# Qilin.net
KiCad netlist of a schematic drawn in Altium Designer
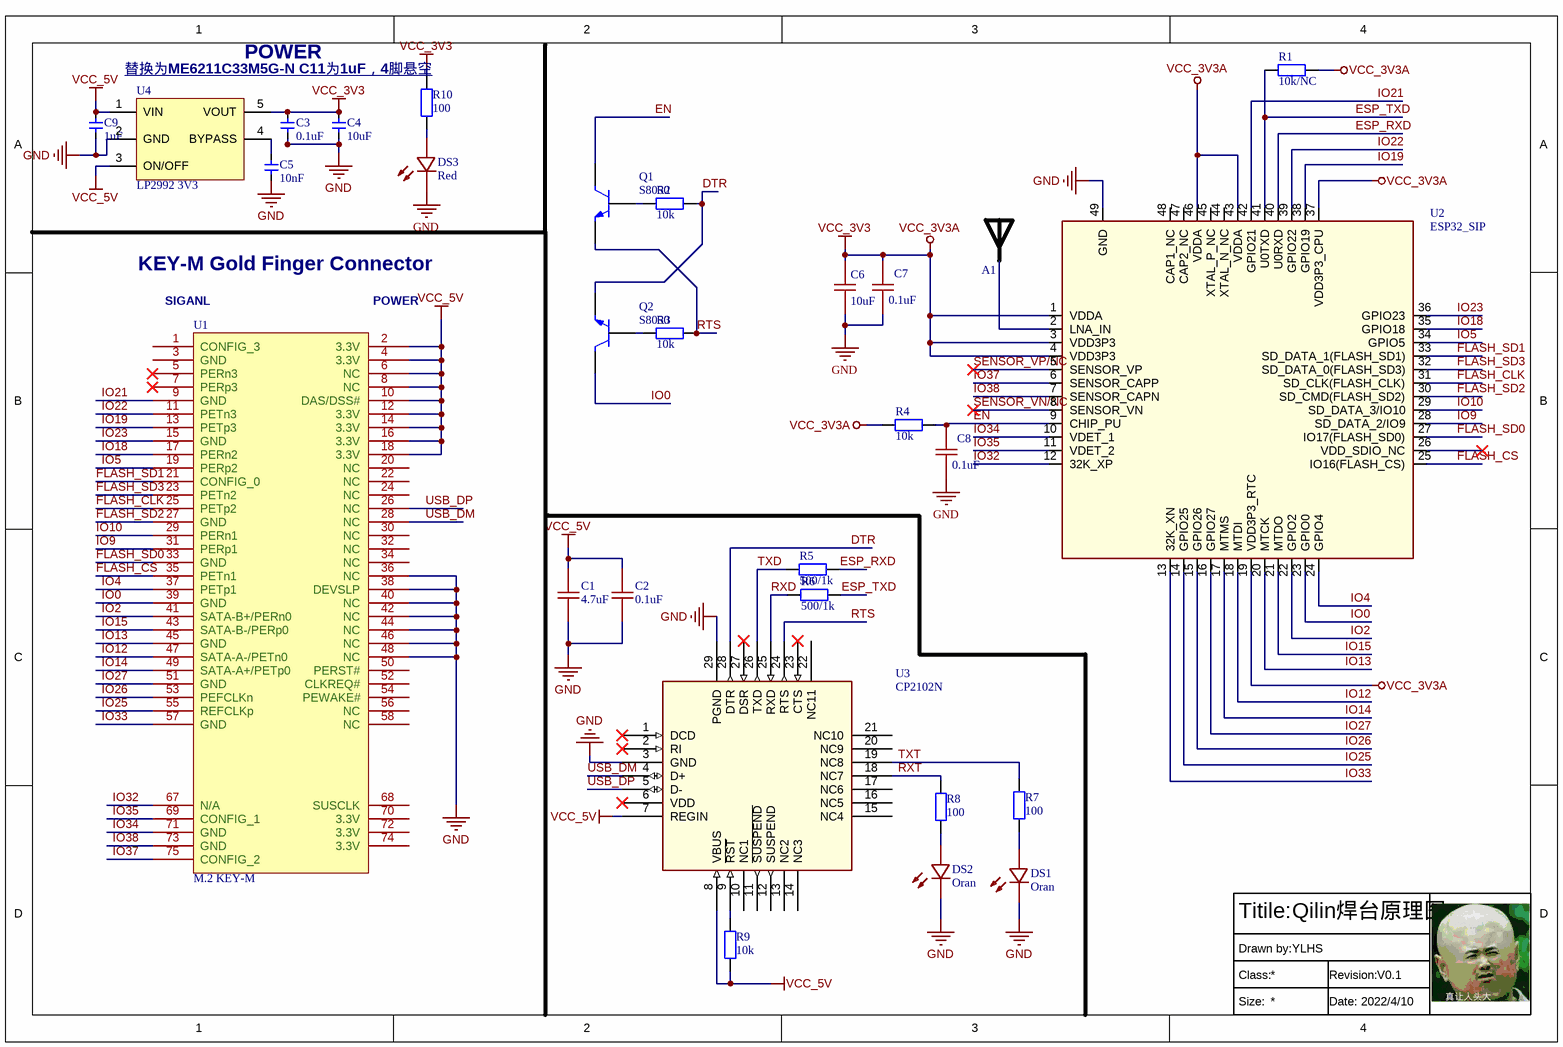
[diagram p0: Qilin.SchDoc]

(export (version "E")
  (design (tool "Eeschema 10.0.6"))
  (components
    (comp (ref "A1")
      (value "RAINSUN")
      (footprint "ANT-Rainsun-AN5120")
      (libsource (lib "common_schlib") (part "ANT-Rainsun-AP5120"))
    )
    (comp (ref "C1")
      (value "4.7uF")
      (footprint "Cap(0402)")
      (description "贴片电容0402")
      (libsource (lib "common_schlib") (part "Cap(0402)"))
    )
    (comp (ref "C2")
      (value "0.1uF")
      (footprint "Cap(0402)")
      (description "贴片电容0402")
      (libsource (lib "common_schlib") (part "Cap(0402)"))
    )
    (comp (ref "C3")
      (value "0.1uF")
      (footprint "CAP_0402")
      (description "Capacitor")
      (libsource (lib "common_schlib") (part "电容-0402"))
    )
    (comp (ref "C4")
      (value "10uF")
      (footprint "CAP_0402")
      (description "Capacitor")
      (libsource (lib "common_schlib") (part "电容-0402"))
    )
    (comp (ref "C5")
      (value "10nF")
      (footprint "CAP_0402")
      (description "Capacitor")
      (libsource (lib "common_schlib") (part "电容-0402"))
    )
    (comp (ref "C6")
      (value "10uF")
      (footprint "Cap(0402)")
      (description "贴片电容0402")
      (libsource (lib "common_schlib") (part "Cap(0402)"))
    )
    (comp (ref "C7")
      (value "0.1uF")
      (footprint "Cap(0402)")
      (description "贴片电容0402")
      (libsource (lib "common_schlib") (part "Cap(0402)"))
    )
    (comp (ref "C8")
      (value "0.1uF")
      (footprint "Cap(0402)")
      (description "贴片电容0402")
      (libsource (lib "common_schlib") (part "Cap(0402)"))
    )
    (comp (ref "C9")
      (value "1uF")
      (footprint "CAP_0402")
      (description "Capacitor")
      (libsource (lib "common_schlib") (part "电容-0402"))
    )
    (comp (ref "DS1")
      (value "Oran")
      (footprint "LED(0402)")
      (libsource (lib "common_schlib") (part "LED_Orange"))
    )
    (comp (ref "DS2")
      (value "Oran")
      (footprint "LED(0402)")
      (libsource (lib "common_schlib") (part "LED_Orange"))
    )
    (comp (ref "DS3")
      (value "Red")
      (footprint "LED(0402)")
      (libsource (lib "common_schlib") (part "LED_Red"))
    )
    (comp (ref "Q1")
      (value "S8050")
      (footprint "SOT23-3")
      (description "NPN")
      (libsource (lib "common_schlib") (part "S8050"))
    )
    (comp (ref "Q2")
      (value "S8050")
      (footprint "SOT23-3")
      (description "NPN")
      (libsource (lib "common_schlib") (part "S8050"))
    )
    (comp (ref "R1")
      (value "10k/NC")
      (footprint "Res(0402)")
      (description "Res(0402)")
      (fields (field (name "Comment") "10K"))
      (libsource (lib "common_schlib") (part "Res(0402)"))
    )
    (comp (ref "R2")
      (value "10k")
      (footprint "Res(0402)")
      (description "Res(0402)")
      (fields (field (name "Comment") "10K"))
      (libsource (lib "common_schlib") (part "Res(0402)"))
    )
    (comp (ref "R3")
      (value "10k")
      (footprint "Res(0402)")
      (description "Res(0402)")
      (fields (field (name "Comment") "10K"))
      (libsource (lib "common_schlib") (part "Res(0402)"))
    )
    (comp (ref "R4")
      (value "10k")
      (footprint "Res(0402)")
      (description "Res(0402)")
      (fields (field (name "Comment") "10K"))
      (libsource (lib "common_schlib") (part "Res(0402)"))
    )
    (comp (ref "R5")
      (value "500/1k")
      (footprint "Res(0402)")
      (description "Res(0402)")
      (fields (field (name "Comment") "500R"))
      (libsource (lib "common_schlib") (part "Res(0402)"))
    )
    (comp (ref "R6")
      (value "500/1k")
      (footprint "Res(0402)")
      (description "Res(0402)")
      (fields (field (name "Comment") "500R"))
      (libsource (lib "common_schlib") (part "Res(0402)"))
    )
    (comp (ref "R7")
      (value "100")
      (footprint "Res(0402)")
      (description "Res(0402)")
      (fields (field (name "Comment") "100R"))
      (libsource (lib "") (part "Res(0402)_1"))
    )
    (comp (ref "R8")
      (value "100")
      (footprint "Res(0402)")
      (description "Res(0402)")
      (fields (field (name "Comment") "100R"))
      (libsource (lib "") (part "Res(0402)_1"))
    )
    (comp (ref "R9")
      (value "10k")
      (footprint "Res(0402)")
      (description "Res(0402)")
      (fields (field (name "Comment") "10K"))
      (libsource (lib "") (part "Res(0402)_2"))
    )
    (comp (ref "R10")
      (value "100")
      (footprint "Res(0402)")
      (description "Res(0402)")
      (fields (field (name "Comment") "100R"))
      (libsource (lib "") (part "Res(0402)_1"))
    )
    (comp (ref "U1")
      (value "M.2 KEY-M")
      (footprint "M.2")
      (description "NGFF M.2 KEY-M")
      (libsource (lib "common_schlib") (part "M.2 KEY-M"))
    )
    (comp (ref "U2")
      (value "ESP32_SIP")
      (footprint "QFN-48 7*7")
      (libsource (lib "common_schlib") (part "ESP32-PICO-D4"))
    )
    (comp (ref "U3")
      (value "CP2102N")
      (footprint "CP2102N")
      (description "USB转串口")
      (libsource (lib "common_schlib") (part "CP2102N"))
    )
    (comp (ref "U4")
      (value "LP2992 3V3")
      (footprint "SOT23-5")
      (description "LDO")
      (libsource (lib "common_schlib") (part "LP2992"))
    )
  )
  (nets
    (net (code "1") (name "/DTR") (class "Default")
      (node (ref "Q2") (pin "2") (pinfunction "E_2") (pintype "passive"))
      (node (ref "R2") (pin "2") (pinfunction "2_2") (pintype "passive"))
      (node (ref "U3") (pin "28") (pinfunction "DTR_28") (pintype "output"))
    )
    (net (code "2") (name "/EN") (class "Default")
      (node (ref "C8") (pin "2") (pinfunction "2_2") (pintype "passive"))
      (node (ref "Q1") (pin "3") (pinfunction "C_3") (pintype "passive"))
      (node (ref "R4") (pin "2") (pinfunction "2_2") (pintype "passive"))
      (node (ref "U2") (pin "9") (pinfunction "CHIP_PU_9") (pintype "passive"))
    )
    (net (code "3") (name "/ESP_RXD") (class "Default")
      (node (ref "R5") (pin "2") (pinfunction "2_2") (pintype "passive"))
      (node (ref "U2") (pin "40") (pinfunction "U0RXD_40") (pintype "power_in"))
    )
    (net (code "4") (name "/ESP_TXD") (class "Default")
      (node (ref "R1") (pin "1") (pinfunction "1_1") (pintype "passive"))
      (node (ref "R6") (pin "2") (pinfunction "2_2") (pintype "passive"))
      (node (ref "U2") (pin "41") (pinfunction "U0TXD_41") (pintype "power_in"))
    )
    (net (code "5") (name "/FLASH_CLK") (class "Default")
      (node (ref "U1") (pin "25") (pinfunction "PETp2_25") (pintype "passive"))
      (node (ref "U2") (pin "31") (pinfunction "SD_CLK(FLASH_CLK)_31") (pintype "passive"))
    )
    (net (code "6") (name "/FLASH_CS") (class "Default")
      (node (ref "U1") (pin "35") (pinfunction "PETn1_35") (pintype "passive"))
      (node (ref "U2") (pin "25") (pinfunction "IO16(FLASH_CS)_25") (pintype "passive"))
    )
    (net (code "7") (name "/FLASH_SD0") (class "Default")
      (node (ref "U1") (pin "33") (pinfunction "GND_33") (pintype "passive"))
      (node (ref "U2") (pin "27") (pinfunction "IO17(FLASH_SD0)_27") (pintype "passive"))
    )
    (net (code "8") (name "/FLASH_SD1") (class "Default")
      (node (ref "U1") (pin "21") (pinfunction "CONFIG_0_21") (pintype "passive"))
      (node (ref "U2") (pin "33") (pinfunction "SD_DATA_1(FLASH_SD1)_33") (pintype "passive"))
    )
    (net (code "9") (name "/FLASH_SD2") (class "Default")
      (node (ref "U1") (pin "27") (pinfunction "GND_27") (pintype "passive"))
      (node (ref "U2") (pin "30") (pinfunction "SD_CMD(FLASH_SD2)_30") (pintype "passive"))
    )
    (net (code "10") (name "/FLASH_SD3") (class "Default")
      (node (ref "U1") (pin "23") (pinfunction "PETn2_23") (pintype "passive"))
      (node (ref "U2") (pin "32") (pinfunction "SD_DATA_0(FLASH_SD3)_32") (pintype "passive"))
    )
    (net (code "11") (name "/IO0") (class "Default")
      (node (ref "Q2") (pin "3") (pinfunction "C_3") (pintype "passive"))
      (node (ref "U1") (pin "39") (pinfunction "GND_39") (pintype "passive"))
      (node (ref "U2") (pin "23") (pinfunction "GPIO0_23") (pintype "passive"))
    )
    (net (code "12") (name "/IO2") (class "Default")
      (node (ref "U1") (pin "41") (pinfunction "SATA-B+/PERn0_41") (pintype "passive"))
      (node (ref "U2") (pin "22") (pinfunction "GPIO2_22") (pintype "passive"))
    )
    (net (code "13") (name "/IO4") (class "Default")
      (node (ref "U1") (pin "37") (pinfunction "PETp1_37") (pintype "passive"))
      (node (ref "U2") (pin "24") (pinfunction "GPIO4_24") (pintype "passive"))
    )
    (net (code "14") (name "/IO5") (class "Default")
      (node (ref "U1") (pin "19") (pinfunction "PERp2_19") (pintype "passive"))
      (node (ref "U2") (pin "34") (pinfunction "GPIO5_34") (pintype "passive"))
    )
    (net (code "15") (name "/IO9") (class "Default")
      (node (ref "U1") (pin "31") (pinfunction "PERp1_31") (pintype "passive"))
      (node (ref "U2") (pin "28") (pinfunction "SD_DATA_2/IO9_28") (pintype "passive"))
    )
    (net (code "16") (name "/IO10") (class "Default")
      (node (ref "U1") (pin "29") (pinfunction "PERn1_29") (pintype "passive"))
      (node (ref "U2") (pin "29") (pinfunction "SD_DATA_3/IO10_29") (pintype "passive"))
    )
    (net (code "17") (name "/IO12") (class "Default")
      (node (ref "U1") (pin "47") (pinfunction "SATA-A-/PETn0_47") (pintype "passive"))
      (node (ref "U2") (pin "18") (pinfunction "MTDI_18") (pintype "passive"))
    )
    (net (code "18") (name "/IO13") (class "Default")
      (node (ref "U1") (pin "45") (pinfunction "GND_45") (pintype "passive"))
      (node (ref "U2") (pin "20") (pinfunction "MTCK_20") (pintype "passive"))
    )
    (net (code "19") (name "/IO14") (class "Default")
      (node (ref "U1") (pin "49") (pinfunction "SATA-A+/PETp0_49") (pintype "passive"))
      (node (ref "U2") (pin "17") (pinfunction "MTMS_17") (pintype "passive"))
    )
    (net (code "20") (name "/IO15") (class "Default")
      (node (ref "U1") (pin "43") (pinfunction "SATA-B-/PERp0_43") (pintype "passive"))
      (node (ref "U2") (pin "21") (pinfunction "MTDO_21") (pintype "passive"))
    )
    (net (code "21") (name "/IO18") (class "Default")
      (node (ref "U1") (pin "17") (pinfunction "PERn2_17") (pintype "passive"))
      (node (ref "U2") (pin "35") (pinfunction "GPIO18_35") (pintype "passive"))
    )
    (net (code "22") (name "/IO19") (class "Default")
      (node (ref "U1") (pin "13") (pinfunction "PETp3_13") (pintype "passive"))
      (node (ref "U2") (pin "38") (pinfunction "GPIO19_38") (pintype "passive"))
    )
    (net (code "23") (name "/IO21") (class "Default")
      (node (ref "U1") (pin "9") (pinfunction "GND_9") (pintype "passive"))
      (node (ref "U2") (pin "42") (pinfunction "GPIO21_42") (pintype "passive"))
    )
    (net (code "24") (name "/IO22") (class "Default")
      (node (ref "U1") (pin "11") (pinfunction "PETn3_11") (pintype "passive"))
      (node (ref "U2") (pin "39") (pinfunction "GPIO22_39") (pintype "passive"))
    )
    (net (code "25") (name "/IO23") (class "Default")
      (node (ref "U1") (pin "15") (pinfunction "GND_15") (pintype "passive"))
      (node (ref "U2") (pin "36") (pinfunction "GPIO23_36") (pintype "passive"))
    )
    (net (code "26") (name "/IO25") (class "Default")
      (node (ref "U1") (pin "55") (pinfunction "REFCLKp_55") (pintype "passive"))
      (node (ref "U2") (pin "14") (pinfunction "GPIO25_14") (pintype "passive"))
    )
    (net (code "27") (name "/IO26") (class "Default")
      (node (ref "U1") (pin "53") (pinfunction "PEFCLKn_53") (pintype "passive"))
      (node (ref "U2") (pin "15") (pinfunction "GPIO26_15") (pintype "passive"))
    )
    (net (code "28") (name "/IO27") (class "Default")
      (node (ref "U1") (pin "51") (pinfunction "GND_51") (pintype "passive"))
      (node (ref "U2") (pin "16") (pinfunction "GPIO27_16") (pintype "passive"))
    )
    (net (code "29") (name "/IO32") (class "Default")
      (node (ref "U1") (pin "67") (pinfunction "N/A_67") (pintype "passive"))
      (node (ref "U2") (pin "12") (pinfunction "32K_XP_12") (pintype "passive"))
    )
    (net (code "30") (name "/IO33") (class "Default")
      (node (ref "U1") (pin "57") (pinfunction "GND_57") (pintype "passive"))
      (node (ref "U2") (pin "13") (pinfunction "32K_XN_13") (pintype "passive"))
    )
    (net (code "31") (name "/IO34") (class "Default")
      (node (ref "U1") (pin "71") (pinfunction "GND_71") (pintype "passive"))
      (node (ref "U2") (pin "10") (pinfunction "VDET_1_10") (pintype "passive"))
    )
    (net (code "32") (name "/IO35") (class "Default")
      (node (ref "U1") (pin "69") (pinfunction "CONFIG_1_69") (pintype "passive"))
      (node (ref "U2") (pin "11") (pinfunction "VDET_2_11") (pintype "passive"))
    )
    (net (code "33") (name "/IO37") (class "Default")
      (node (ref "U1") (pin "75") (pinfunction "CONFIG_2_75") (pintype "passive"))
      (node (ref "U2") (pin "6") (pinfunction "SENSOR_CAPP_6") (pintype "passive"))
    )
    (net (code "34") (name "/IO38") (class "Default")
      (node (ref "U1") (pin "73") (pinfunction "GND_73") (pintype "passive"))
      (node (ref "U2") (pin "7") (pinfunction "SENSOR_CAPN_7") (pintype "passive"))
    )
    (net (code "35") (name "/RTS") (class "Default")
      (node (ref "Q1") (pin "2") (pinfunction "E_2") (pintype "passive"))
      (node (ref "R3") (pin "2") (pinfunction "2_2") (pintype "passive"))
      (node (ref "U3") (pin "24") (pinfunction "RTS_24") (pintype "output"))
    )
    (net (code "36") (name "/RXD") (class "Default")
      (node (ref "R6") (pin "1") (pinfunction "1_1") (pintype "passive"))
      (node (ref "U3") (pin "25") (pinfunction "RXD_25") (pintype "input"))
    )
    (net (code "37") (name "/RXT") (class "Default")
      (node (ref "R8") (pin "2") (pinfunction "2_2") (pintype "passive"))
      (node (ref "U3") (pin "18") (pinfunction "NC7_18") (pintype "passive"))
    )
    (net (code "38") (name "/SENSOR_VN{slash}NC") (class "Default")
      (node (ref "U2") (pin "8") (pinfunction "SENSOR_VN_8") (pintype "passive+no_connect"))
    )
    (net (code "39") (name "/SENSOR_VP{slash}NC") (class "Default")
      (node (ref "U2") (pin "5") (pinfunction "SENSOR_VP_5") (pintype "passive+no_connect"))
    )
    (net (code "40") (name "/TXD") (class "Default")
      (node (ref "R5") (pin "1") (pinfunction "1_1") (pintype "passive"))
      (node (ref "U3") (pin "26") (pinfunction "TXD_26") (pintype "output"))
    )
    (net (code "41") (name "/TXT") (class "Default")
      (node (ref "R7") (pin "2") (pinfunction "2_2") (pintype "passive"))
      (node (ref "U3") (pin "19") (pinfunction "NC8_19") (pintype "passive"))
    )
    (net (code "42") (name "/USB_DM") (class "Default")
      (node (ref "U1") (pin "28") (pinfunction "NC_28") (pintype "passive"))
      (node (ref "U3") (pin "4") (pinfunction "D+_4") (pintype "bidirectional"))
    )
    (net (code "43") (name "/USB_DP") (class "Default")
      (node (ref "U1") (pin "26") (pinfunction "NC_26") (pintype "passive"))
      (node (ref "U3") (pin "5") (pinfunction "D-_5") (pintype "bidirectional"))
    )
    (net (code "44") (name "GND") (class "Default")
      (node (ref "C1") (pin "1") (pinfunction "1_1") (pintype "passive"))
      (node (ref "C2") (pin "1") (pinfunction "1_1") (pintype "passive"))
      (node (ref "C3") (pin "1") (pinfunction "1_1") (pintype "passive"))
      (node (ref "C4") (pin "1") (pinfunction "1_1") (pintype "passive"))
      (node (ref "C5") (pin "1") (pinfunction "1_1") (pintype "passive"))
      (node (ref "C6") (pin "1") (pinfunction "1_1") (pintype "passive"))
      (node (ref "C7") (pin "1") (pinfunction "1_1") (pintype "passive"))
      (node (ref "C8") (pin "1") (pinfunction "1_1") (pintype "passive"))
      (node (ref "C9") (pin "1") (pinfunction "1_1") (pintype "passive"))
      (node (ref "DS1") (pin "1") (pinfunction "C_1") (pintype "passive"))
      (node (ref "DS2") (pin "1") (pinfunction "C_1") (pintype "passive"))
      (node (ref "DS3") (pin "1") (pinfunction "C_1") (pintype "passive"))
      (node (ref "U1") (pin "36") (pinfunction "NC_36") (pintype "passive"))
      (node (ref "U1") (pin "38") (pinfunction "DEVSLP_38") (pintype "passive"))
      (node (ref "U1") (pin "40") (pinfunction "NC_40") (pintype "passive"))
      (node (ref "U1") (pin "42") (pinfunction "NC_42") (pintype "passive"))
      (node (ref "U1") (pin "44") (pinfunction "NC_44") (pintype "passive"))
      (node (ref "U1") (pin "46") (pinfunction "NC_46") (pintype "passive"))
      (node (ref "U1") (pin "48") (pinfunction "NC_48") (pintype "passive"))
      (node (ref "U2") (pin "49") (pinfunction "GND_49") (pintype "power_in"))
      (node (ref "U3") (pin "29") (pinfunction "PGND_29") (pintype "power_in"))
      (node (ref "U3") (pin "3") (pinfunction "GND_3") (pintype "power_in"))
      (node (ref "U4") (pin "2") (pinfunction "GND_2") (pintype "passive"))
    )
    (net (code "45") (name "Net-(DS1-A)") (class "Default")
      (node (ref "DS1") (pin "2") (pinfunction "A_2") (pintype "passive"))
      (node (ref "R7") (pin "1") (pinfunction "1_1") (pintype "passive"))
    )
    (net (code "46") (name "Net-(DS2-A)") (class "Default")
      (node (ref "DS2") (pin "2") (pinfunction "A_2") (pintype "passive"))
      (node (ref "R8") (pin "1") (pinfunction "1_1") (pintype "passive"))
    )
    (net (code "47") (name "Net-(DS3-A)") (class "Default")
      (node (ref "DS3") (pin "2") (pinfunction "A_2") (pintype "passive"))
      (node (ref "R10") (pin "1") (pinfunction "1_1") (pintype "passive"))
    )
    (net (code "48") (name "Net-(Q1-B)") (class "Default")
      (node (ref "Q1") (pin "1") (pinfunction "B_1") (pintype "passive"))
      (node (ref "R2") (pin "1") (pinfunction "1_1") (pintype "passive"))
    )
    (net (code "49") (name "Net-(Q2-B)") (class "Default")
      (node (ref "Q2") (pin "1") (pinfunction "B_1") (pintype "passive"))
      (node (ref "R3") (pin "1") (pinfunction "1_1") (pintype "passive"))
    )
    (net (code "50") (name "Net-(U2-LNA_IN)") (class "Default")
      (node (ref "A1") (pin "1") (pinfunction "1_1") (pintype "passive"))
      (node (ref "U2") (pin "2") (pinfunction "LNA_IN_2") (pintype "passive"))
    )
    (net (code "51") (name "Net-(U3-~{RST})") (class "Default")
      (node (ref "R9") (pin "1") (pinfunction "1_1") (pintype "passive"))
      (node (ref "U3") (pin "9") (pinfunction "~{RST}_9") (pintype "input"))
    )
    (net (code "52") (name "Net-(U4-BYPASS)") (class "Default")
      (node (ref "C5") (pin "2") (pinfunction "2_2") (pintype "passive"))
      (node (ref "U4") (pin "4") (pinfunction "BYPASS_4") (pintype "passive"))
    )
    (net (code "53") (name "VCC_3V3") (class "Default")
      (node (ref "C3") (pin "2") (pinfunction "2_2") (pintype "passive"))
      (node (ref "C4") (pin "2") (pinfunction "2_2") (pintype "passive"))
      (node (ref "C6") (pin "2") (pinfunction "2_2") (pintype "passive"))
      (node (ref "C7") (pin "2") (pinfunction "2_2") (pintype "passive"))
      (node (ref "R1") (pin "2") (pinfunction "2_2") (pintype "passive"))
      (node (ref "R10") (pin "2") (pinfunction "2_2") (pintype "passive"))
      (node (ref "R4") (pin "1") (pinfunction "1_1") (pintype "passive"))
      (node (ref "U2") (pin "1") (pinfunction "VDDA_1") (pintype "power_in"))
      (node (ref "U2") (pin "19") (pinfunction "VDD3P3_RTC_19") (pintype "power_in"))
      (node (ref "U2") (pin "3") (pinfunction "VDD3P3_3") (pintype "power_in"))
      (node (ref "U2") (pin "37") (pinfunction "VDD3P3_CPU_37") (pintype "power_in"))
      (node (ref "U2") (pin "4") (pinfunction "VDD3P3_4") (pintype "power_in"))
      (node (ref "U2") (pin "43") (pinfunction "VDDA_43") (pintype "power_in"))
      (node (ref "U2") (pin "46") (pinfunction "VDDA_46") (pintype "power_in"))
      (node (ref "U4") (pin "5") (pinfunction "VOUT_5") (pintype "passive"))
    )
    (net (code "54") (name "VCC_5V") (class "Default")
      (node (ref "C1") (pin "2") (pinfunction "2_2") (pintype "passive"))
      (node (ref "C2") (pin "2") (pinfunction "2_2") (pintype "passive"))
      (node (ref "C9") (pin "2") (pinfunction "2_2") (pintype "passive"))
      (node (ref "R9") (pin "2") (pinfunction "2_2") (pintype "passive"))
      (node (ref "U1") (pin "10") (pinfunction "DAS/DSS#_10") (pintype "passive"))
      (node (ref "U1") (pin "12") (pinfunction "3.3V_12") (pintype "passive"))
      (node (ref "U1") (pin "14") (pinfunction "3.3V_14") (pintype "passive"))
      (node (ref "U1") (pin "16") (pinfunction "3.3V_16") (pintype "passive"))
      (node (ref "U1") (pin "18") (pinfunction "3.3V_18") (pintype "passive"))
      (node (ref "U1") (pin "2") (pinfunction "3.3V_2") (pintype "passive"))
      (node (ref "U1") (pin "4") (pinfunction "3.3V_4") (pintype "passive"))
      (node (ref "U1") (pin "6") (pinfunction "NC_6") (pintype "passive"))
      (node (ref "U1") (pin "8") (pinfunction "NC_8") (pintype "passive"))
      (node (ref "U3") (pin "7") (pinfunction "REGIN_7") (pintype "power_in"))
      (node (ref "U3") (pin "8") (pinfunction "VBUS_8") (pintype "input"))
      (node (ref "U4") (pin "1") (pinfunction "VIN_1") (pintype "passive"))
      (node (ref "U4") (pin "3") (pinfunction "ON/OFF_3") (pintype "passive"))
    )
    (net (code "55") (name "unconnected-(U1-3.3V-Pad70)") (class "Default")
      (node (ref "U1") (pin "70") (pinfunction "3.3V_70") (pintype "passive"))
    )
    (net (code "56") (name "unconnected-(U1-3.3V-Pad72)") (class "Default")
      (node (ref "U1") (pin "72") (pinfunction "3.3V_72") (pintype "passive"))
    )
    (net (code "57") (name "unconnected-(U1-3.3V-Pad74)") (class "Default")
      (node (ref "U1") (pin "74") (pinfunction "3.3V_74") (pintype "passive"))
    )
    (net (code "58") (name "unconnected-(U1-CLKREQ#-Pad52)") (class "Default")
      (node (ref "U1") (pin "52") (pinfunction "CLKREQ#_52") (pintype "passive"))
    )
    (net (code "59") (name "unconnected-(U1-CONFIG_3-Pad1)") (class "Default")
      (node (ref "U1") (pin "1") (pinfunction "CONFIG_3_1") (pintype "passive"))
    )
    (net (code "60") (name "unconnected-(U1-GND-Pad3)") (class "Default")
      (node (ref "U1") (pin "3") (pinfunction "GND_3") (pintype "passive"))
    )
    (net (code "61") (name "unconnected-(U1-NC-Pad20)") (class "Default")
      (node (ref "U1") (pin "20") (pinfunction "NC_20") (pintype "passive"))
    )
    (net (code "62") (name "unconnected-(U1-NC-Pad22)") (class "Default")
      (node (ref "U1") (pin "22") (pinfunction "NC_22") (pintype "passive"))
    )
    (net (code "63") (name "unconnected-(U1-NC-Pad24)") (class "Default")
      (node (ref "U1") (pin "24") (pinfunction "NC_24") (pintype "passive"))
    )
    (net (code "64") (name "unconnected-(U1-NC-Pad30)") (class "Default")
      (node (ref "U1") (pin "30") (pinfunction "NC_30") (pintype "passive"))
    )
    (net (code "65") (name "unconnected-(U1-NC-Pad32)") (class "Default")
      (node (ref "U1") (pin "32") (pinfunction "NC_32") (pintype "passive"))
    )
    (net (code "66") (name "unconnected-(U1-NC-Pad34)") (class "Default")
      (node (ref "U1") (pin "34") (pinfunction "NC_34") (pintype "passive"))
    )
    (net (code "67") (name "unconnected-(U1-NC-Pad56)") (class "Default")
      (node (ref "U1") (pin "56") (pinfunction "NC_56") (pintype "passive"))
    )
    (net (code "68") (name "unconnected-(U1-NC-Pad58)") (class "Default")
      (node (ref "U1") (pin "58") (pinfunction "NC_58") (pintype "passive"))
    )
    (net (code "69") (name "unconnected-(U1-PERST#-Pad50)") (class "Default")
      (node (ref "U1") (pin "50") (pinfunction "PERST#_50") (pintype "passive"))
    )
    (net (code "70") (name "unconnected-(U1-PERn3-Pad5)") (class "Default")
      (node (ref "U1") (pin "5") (pinfunction "PERn3_5") (pintype "passive+no_connect"))
    )
    (net (code "71") (name "unconnected-(U1-PERp3-Pad7)") (class "Default")
      (node (ref "U1") (pin "7") (pinfunction "PERp3_7") (pintype "passive+no_connect"))
    )
    (net (code "72") (name "unconnected-(U1-PEWAKE#-Pad54)") (class "Default")
      (node (ref "U1") (pin "54") (pinfunction "PEWAKE#_54") (pintype "passive"))
    )
    (net (code "73") (name "unconnected-(U1-SUSCLK-Pad68)") (class "Default")
      (node (ref "U1") (pin "68") (pinfunction "SUSCLK_68") (pintype "passive"))
    )
    (net (code "74") (name "unconnected-(U2-CAP1_NC-Pad48)") (class "Default")
      (node (ref "U2") (pin "48") (pinfunction "CAP1_NC_48") (pintype "passive"))
    )
    (net (code "75") (name "unconnected-(U2-CAP2_NC-Pad47)") (class "Default")
      (node (ref "U2") (pin "47") (pinfunction "CAP2_NC_47") (pintype "passive"))
    )
    (net (code "76") (name "unconnected-(U2-VDD_SDIO_NC-Pad26)") (class "Default")
      (node (ref "U2") (pin "26") (pinfunction "VDD_SDIO_NC_26") (pintype "passive+no_connect"))
    )
    (net (code "77") (name "unconnected-(U2-XTAL_N_NC-Pad44)") (class "Default")
      (node (ref "U2") (pin "44") (pinfunction "XTAL_N_NC_44") (pintype "passive"))
    )
    (net (code "78") (name "unconnected-(U2-XTAL_P_NC-Pad45)") (class "Default")
      (node (ref "U2") (pin "45") (pinfunction "XTAL_P_NC_45") (pintype "passive"))
    )
    (net (code "79") (name "unconnected-(U3-CTS-Pad23)") (class "Default")
      (node (ref "U3") (pin "23") (pinfunction "CTS_23") (pintype "input+no_connect"))
    )
    (net (code "80") (name "unconnected-(U3-DCD-Pad1)") (class "Default")
      (node (ref "U3") (pin "1") (pinfunction "DCD_1") (pintype "input+no_connect"))
    )
    (net (code "81") (name "unconnected-(U3-DSR-Pad27)") (class "Default")
      (node (ref "U3") (pin "27") (pinfunction "DSR_27") (pintype "input+no_connect"))
    )
    (net (code "82") (name "unconnected-(U3-NC1-Pad10)") (class "Default")
      (node (ref "U3") (pin "10") (pinfunction "NC1_10") (pintype "passive"))
    )
    (net (code "83") (name "unconnected-(U3-NC2-Pad13)") (class "Default")
      (node (ref "U3") (pin "13") (pinfunction "NC2_13") (pintype "passive"))
    )
    (net (code "84") (name "unconnected-(U3-NC3-Pad14)") (class "Default")
      (node (ref "U3") (pin "14") (pinfunction "NC3_14") (pintype "passive"))
    )
    (net (code "85") (name "unconnected-(U3-NC4-Pad15)") (class "Default")
      (node (ref "U3") (pin "15") (pinfunction "NC4_15") (pintype "passive"))
    )
    (net (code "86") (name "unconnected-(U3-NC5-Pad16)") (class "Default")
      (node (ref "U3") (pin "16") (pinfunction "NC5_16") (pintype "passive"))
    )
    (net (code "87") (name "unconnected-(U3-NC6-Pad17)") (class "Default")
      (node (ref "U3") (pin "17") (pinfunction "NC6_17") (pintype "passive"))
    )
    (net (code "88") (name "unconnected-(U3-NC9-Pad20)") (class "Default")
      (node (ref "U3") (pin "20") (pinfunction "NC9_20") (pintype "passive"))
    )
    (net (code "89") (name "unconnected-(U3-NC10-Pad21)") (class "Default")
      (node (ref "U3") (pin "21") (pinfunction "NC10_21") (pintype "passive"))
    )
    (net (code "90") (name "unconnected-(U3-NC11-Pad22)") (class "Default")
      (node (ref "U3") (pin "22") (pinfunction "NC11_22") (pintype "passive"))
    )
    (net (code "91") (name "unconnected-(U3-RI-Pad2)") (class "Default")
      (node (ref "U3") (pin "2") (pinfunction "RI_2") (pintype "input+no_connect"))
    )
    (net (code "92") (name "unconnected-(U3-SUSPEND-Pad12)") (class "Default")
      (node (ref "U3") (pin "12") (pinfunction "SUSPEND_12") (pintype "output"))
    )
    (net (code "93") (name "unconnected-(U3-VDD-Pad6)") (class "Default")
      (node (ref "U3") (pin "6") (pinfunction "VDD_6") (pintype "power_in+no_connect"))
    )
    (net (code "94") (name "unconnected-(U3-~{SUSPEND}-Pad11)") (class "Default")
      (node (ref "U3") (pin "11") (pinfunction "~{SUSPEND}_11") (pintype "output"))
    )
  )
)
